# Power_PCB_final.net
KiCad netlist of a schematic drawn in EAGLE
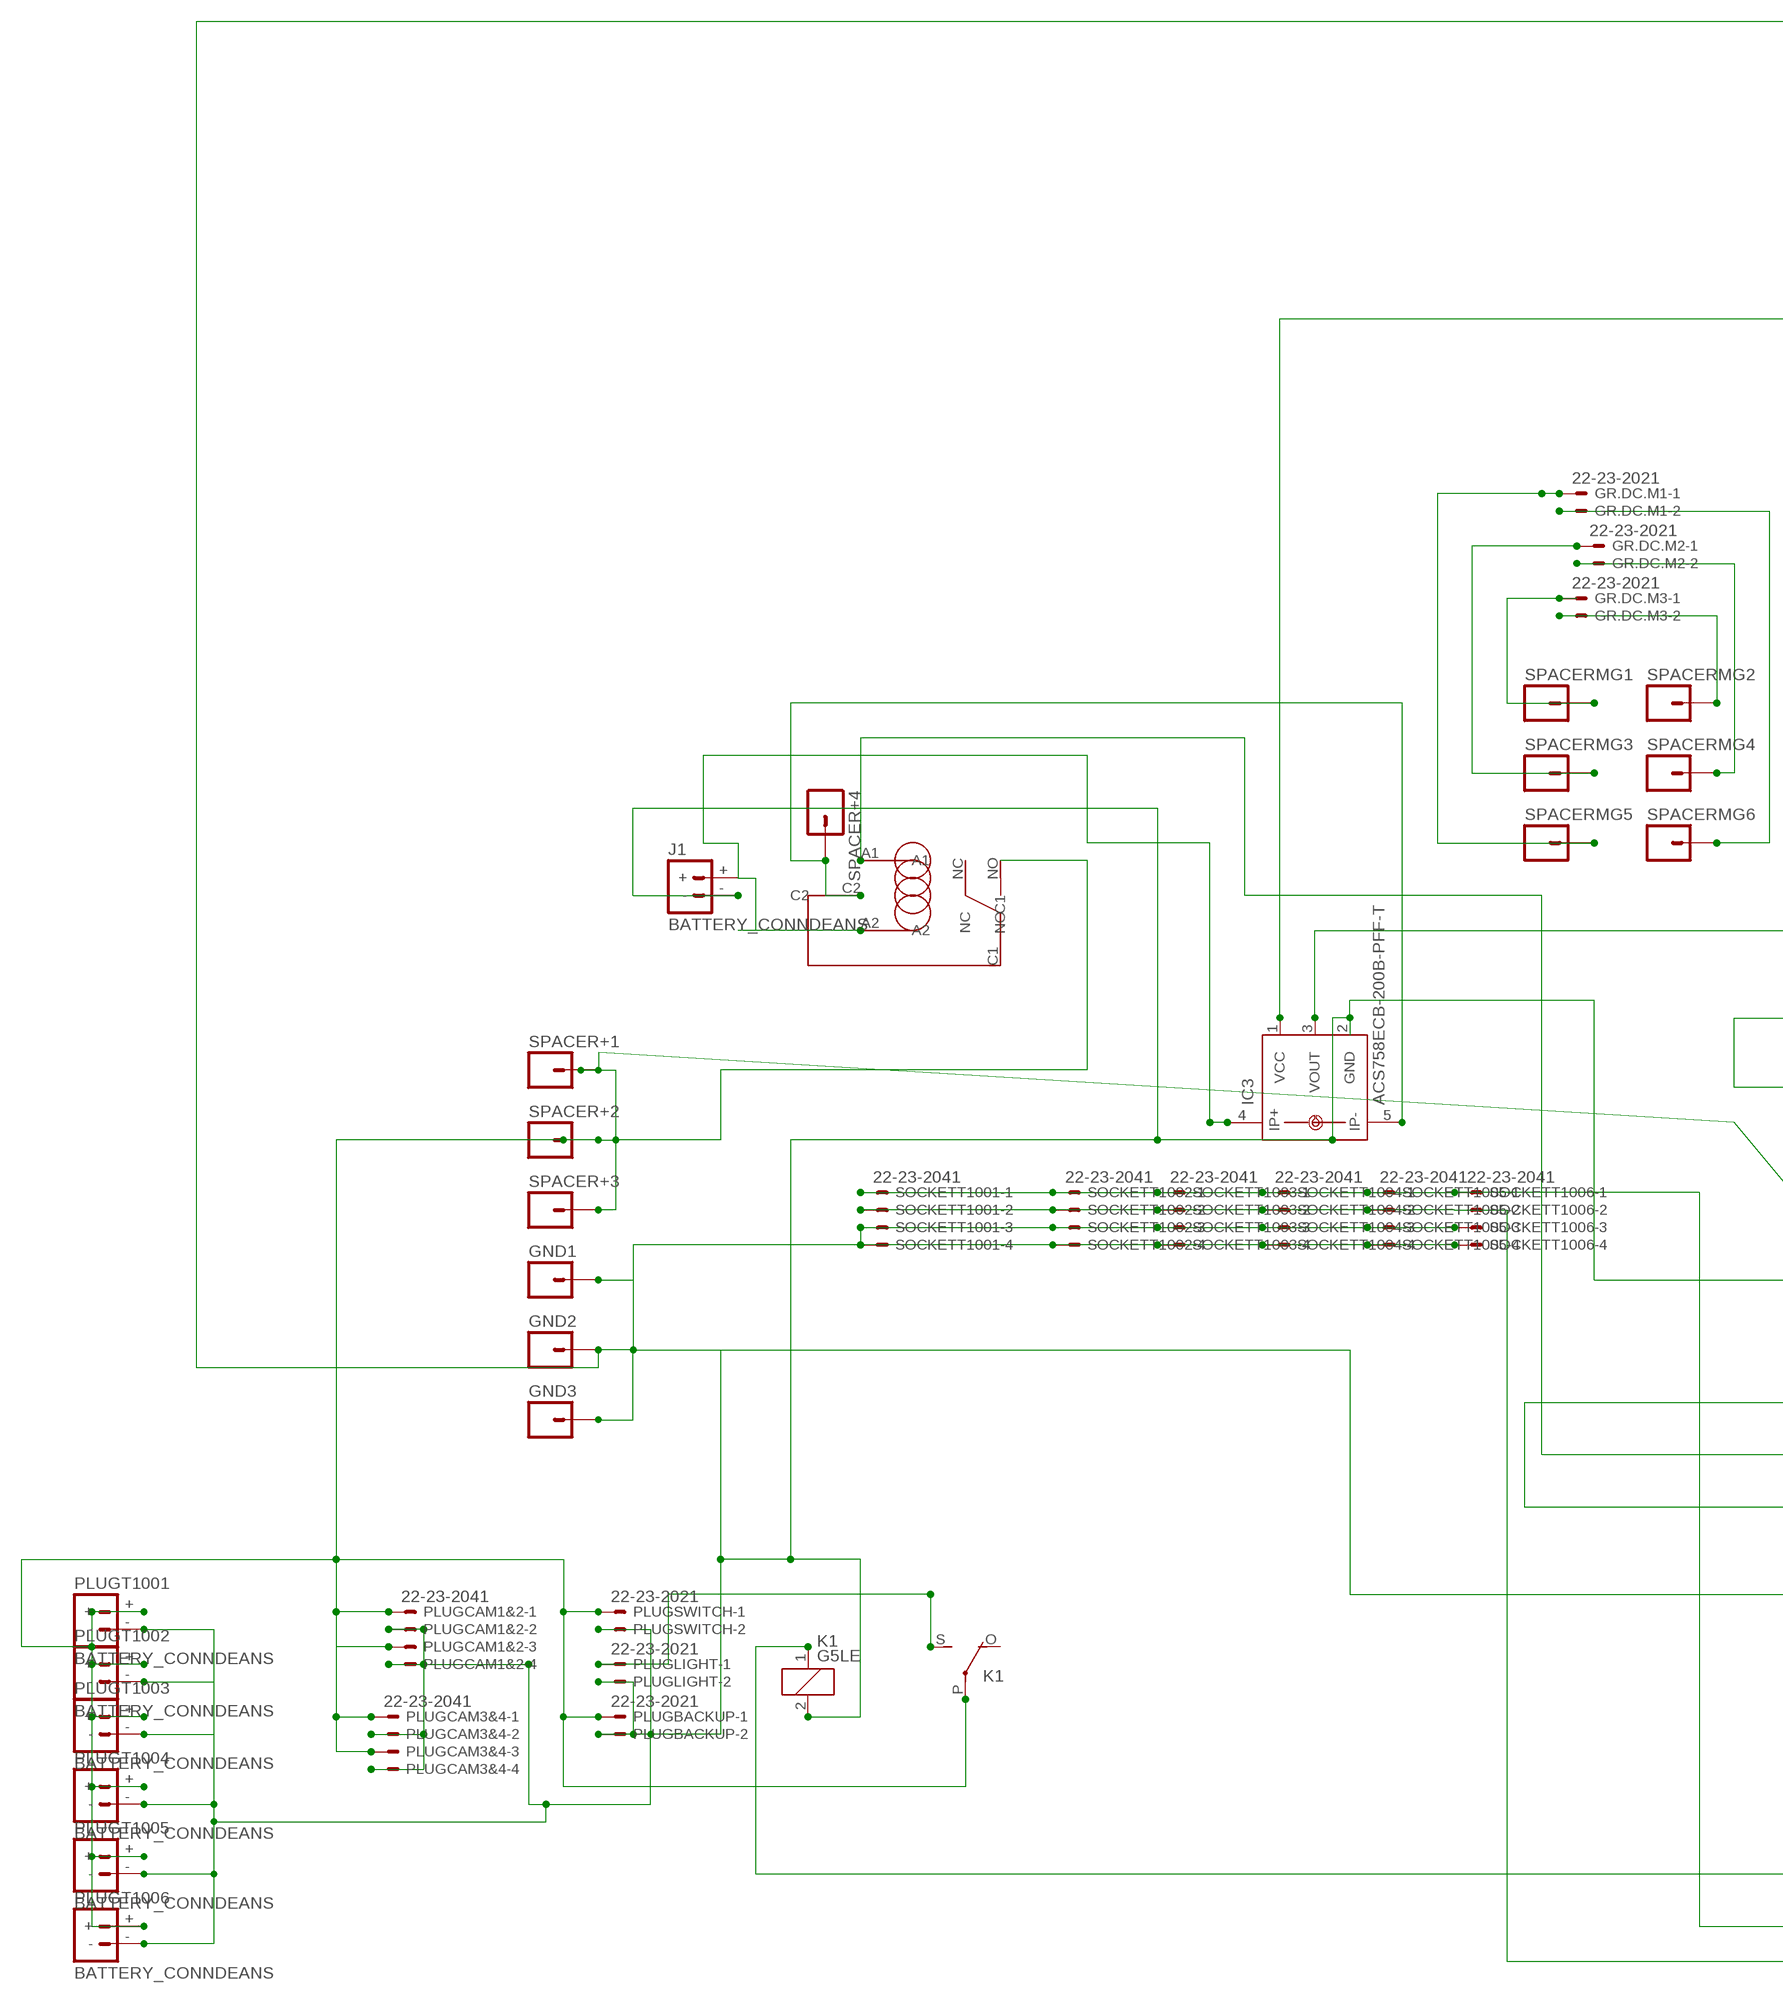
[diagram p0: schematic, sheet 1, part 1 of 2]
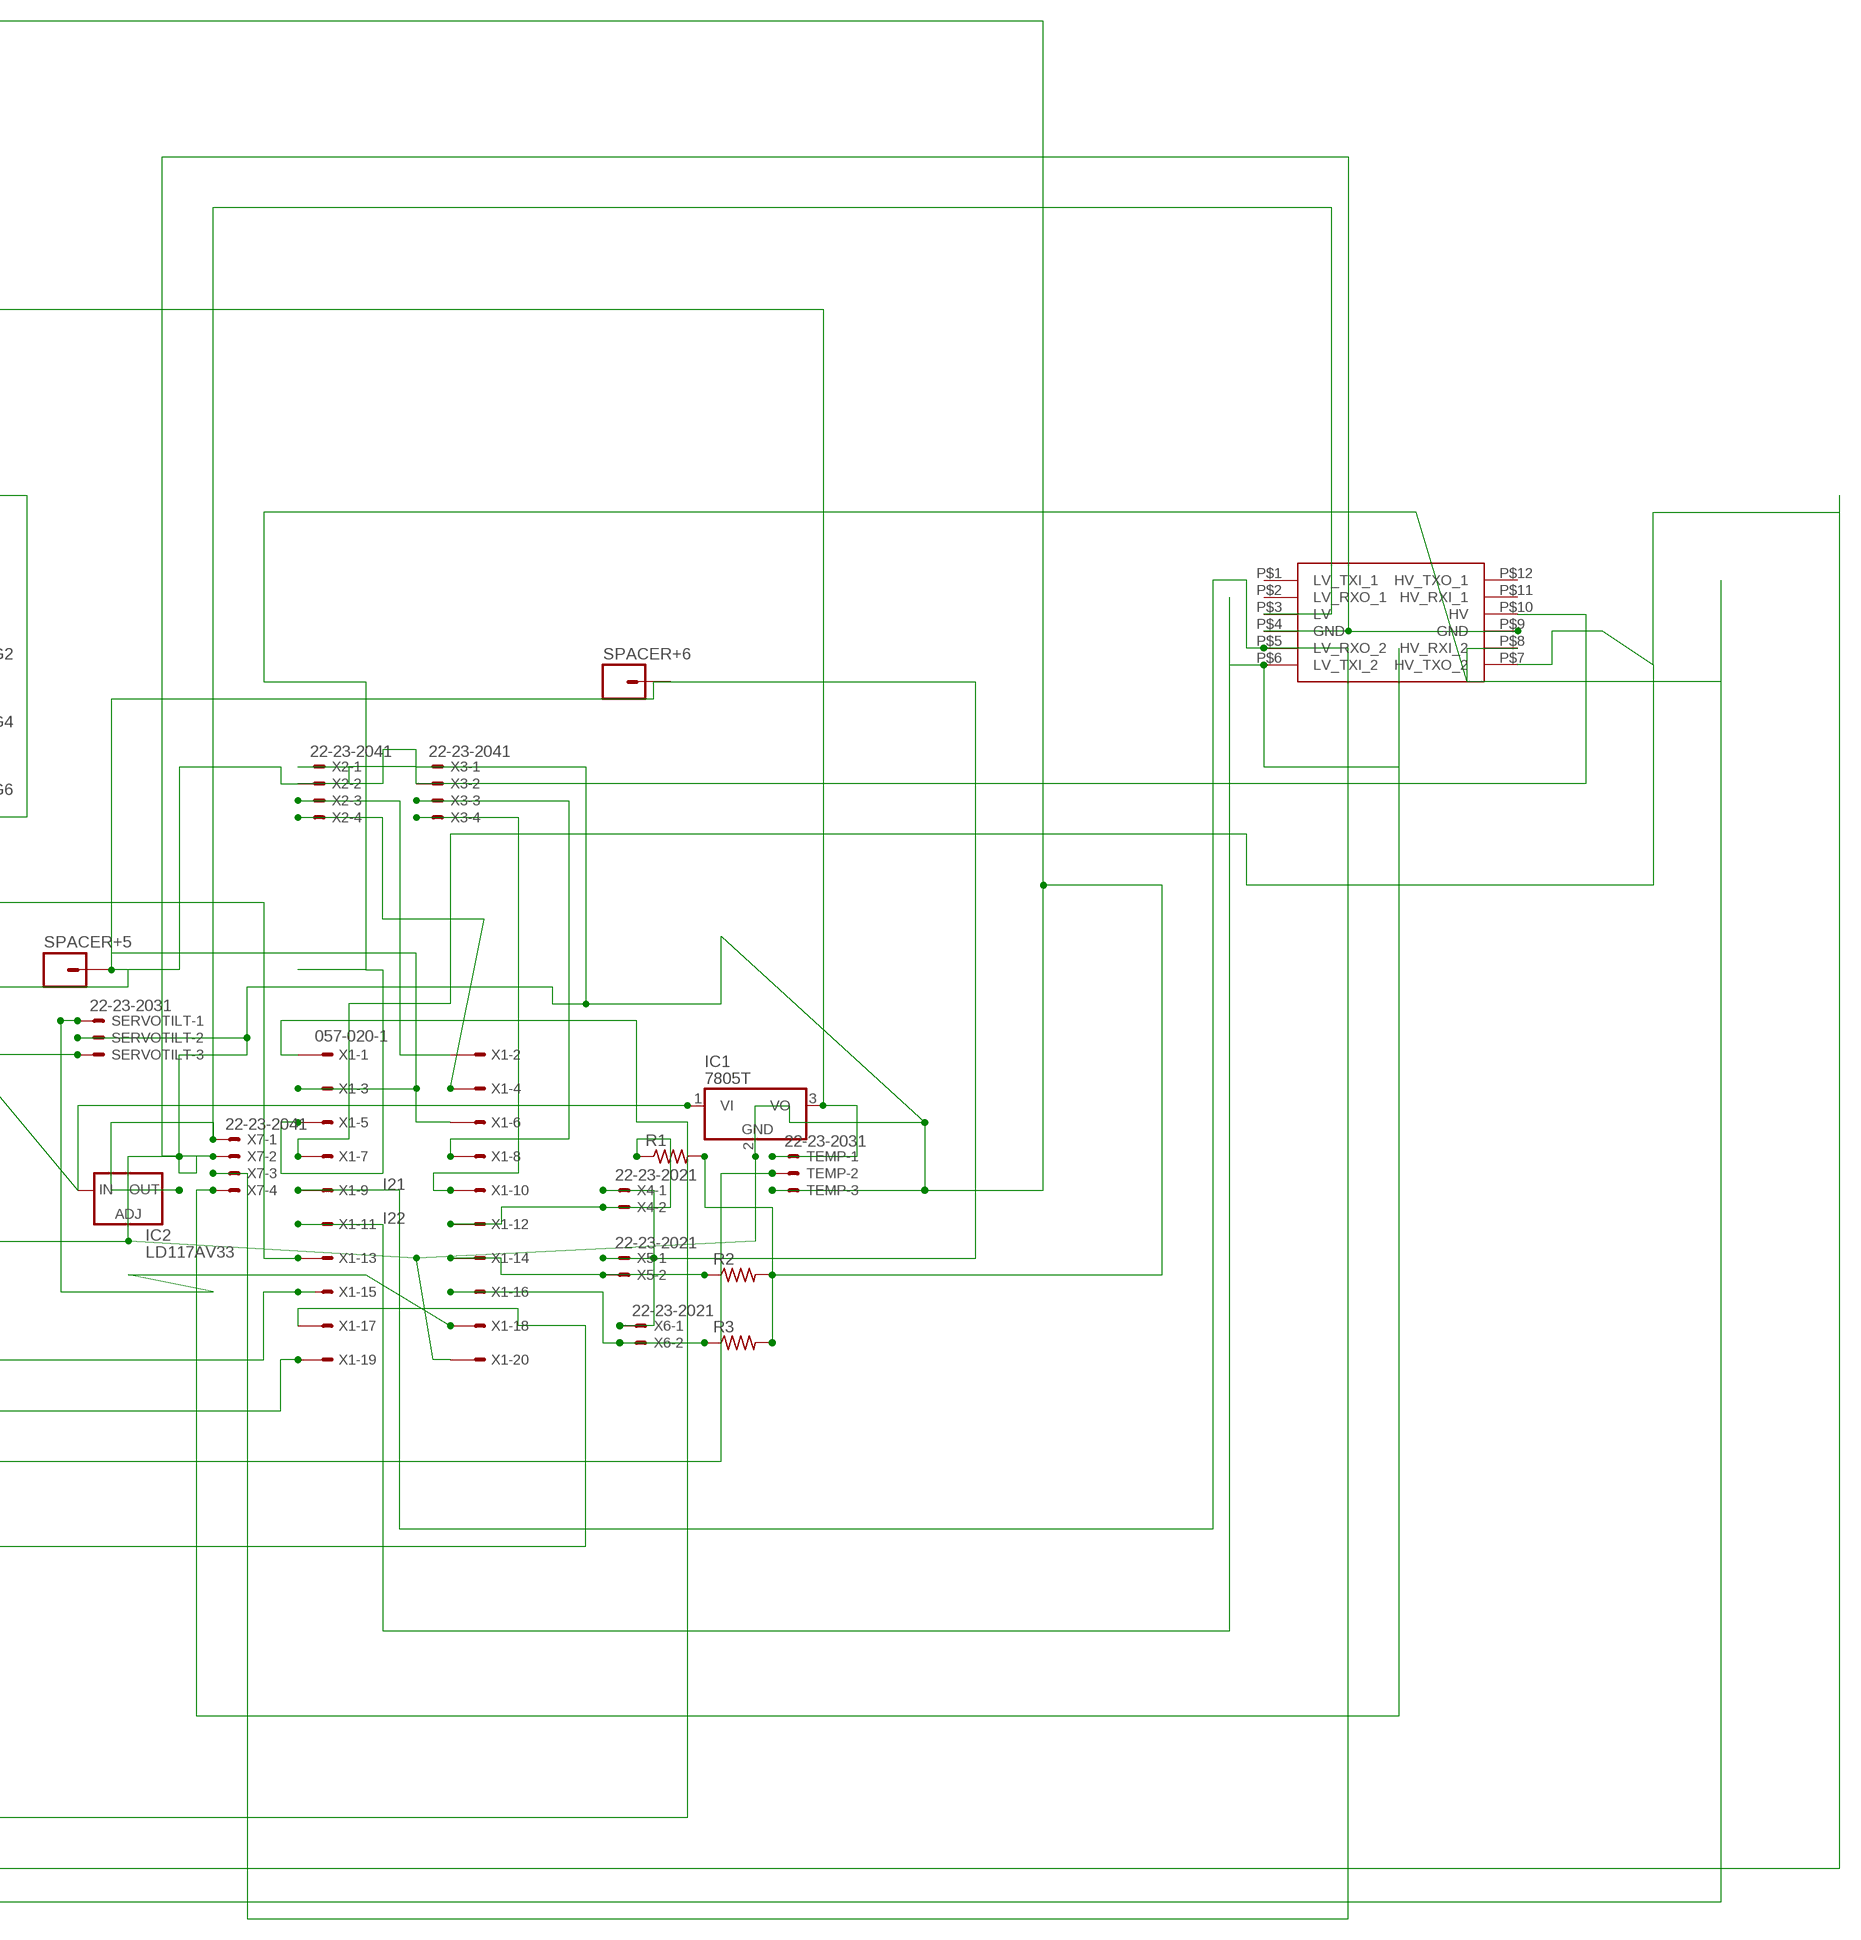
[diagram p1: schematic, sheet 1, part 2 of 2]

(export (version "E")
  (design (tool "Eeschema 10.0.6"))
  (components
    (comp (ref "GND1")
      (value "M01PTH_2MM")
      (footprint "eagle-import:1X01_2MM")
      (libsource (lib "eagle-import") (part "M01PTH_2MM"))
    )
    (comp (ref "GND2")
      (value "M01PTH_2MM")
      (footprint "eagle-import:1X01_2MM")
      (libsource (lib "eagle-import") (part "M01PTH_2MM"))
    )
    (comp (ref "GND3")
      (value "M01PTH_2MM")
      (footprint "eagle-import:1X01_2MM")
      (libsource (lib "eagle-import") (part "M01PTH_2MM"))
    )
    (comp (ref "GR.DC.M1")
      (value "22-23-2021")
      (footprint "eagle-import:22-23-2021")
      (fields (field (name "MF") "MOLEX"))
      (libsource (lib "eagle-import") (part "22-23-2021"))
    )
    (comp (ref "GR.DC.M2")
      (value "22-23-2021")
      (footprint "eagle-import:22-23-2021")
      (fields (field (name "MF") "MOLEX"))
      (libsource (lib "eagle-import") (part "22-23-2021"))
    )
    (comp (ref "GR.DC.M3")
      (value "22-23-2021")
      (footprint "eagle-import:22-23-2021")
      (fields (field (name "MF") "MOLEX"))
      (libsource (lib "eagle-import") (part "22-23-2021"))
    )
    (comp (ref "IC1")
      (value "7805T")
      (footprint "eagle-import:TO220H")
      (libsource (lib "eagle-import") (part "78T05"))
    )
    (comp (ref "IC2")
      (value "LD117AV33")
      (footprint "eagle-import:TO220L1")
      (libsource (lib "eagle-import") (part "LD117A?V33"))
    )
    (comp (ref "IC3")
      (value "ACS758ECB-200B-PFF-T")
      (footprint "eagle-import:CB-PFF")
      (libsource (lib "eagle-import") (part "ACS758ECB-200B-PFF-T"))
    )
    (comp (ref "J1")
      (value "BATTERY_CONNDEANS")
      (footprint "eagle-import:DEANS")
      (libsource (lib "eagle-import") (part "BATTERY_CONNDEANS"))
    )
    (comp (ref "K1")
      (value "G5LE")
      (footprint "eagle-import:G5LE")
      (libsource (lib "eagle-import") (part "G5LE"))
    )
    (comp (ref "PLUGBACKUP")
      (value "22-23-2021")
      (footprint "eagle-import:22-23-2021")
      (fields (field (name "MF") "MOLEX"))
      (libsource (lib "eagle-import") (part "22-23-2021"))
    )
    (comp (ref "PLUGCAM1&2")
      (value "22-23-2041")
      (footprint "eagle-import:22-23-2041")
      (fields (field (name "MF") "MOLEX"))
      (libsource (lib "eagle-import") (part "22-23-2041"))
    )
    (comp (ref "PLUGCAM3&4")
      (value "22-23-2041")
      (footprint "eagle-import:22-23-2041")
      (fields (field (name "MF") "MOLEX"))
      (libsource (lib "eagle-import") (part "22-23-2041"))
    )
    (comp (ref "PLUGLIGHT")
      (value "22-23-2021")
      (footprint "eagle-import:22-23-2021")
      (fields (field (name "MF") "MOLEX"))
      (libsource (lib "eagle-import") (part "22-23-2021"))
    )
    (comp (ref "PLUGSWITCH")
      (value "22-23-2021")
      (footprint "eagle-import:22-23-2021")
      (fields (field (name "MF") "MOLEX"))
      (libsource (lib "eagle-import") (part "22-23-2021"))
    )
    (comp (ref "PLUGT1001")
      (value "BATTERY_CONNDEANS")
      (footprint "eagle-import:DEANS")
      (libsource (lib "eagle-import") (part "BATTERY_CONNDEANS"))
    )
    (comp (ref "PLUGT1002")
      (value "BATTERY_CONNDEANS")
      (footprint "eagle-import:DEANS")
      (libsource (lib "eagle-import") (part "BATTERY_CONNDEANS"))
    )
    (comp (ref "PLUGT1003")
      (value "BATTERY_CONNDEANS")
      (footprint "eagle-import:DEANS")
      (libsource (lib "eagle-import") (part "BATTERY_CONNDEANS"))
    )
    (comp (ref "PLUGT1004")
      (value "BATTERY_CONNDEANS")
      (footprint "eagle-import:DEANS")
      (libsource (lib "eagle-import") (part "BATTERY_CONNDEANS"))
    )
    (comp (ref "PLUGT1005")
      (value "BATTERY_CONNDEANS")
      (footprint "eagle-import:DEANS")
      (libsource (lib "eagle-import") (part "BATTERY_CONNDEANS"))
    )
    (comp (ref "PLUGT1006")
      (value "BATTERY_CONNDEANS")
      (footprint "eagle-import:DEANS")
      (libsource (lib "eagle-import") (part "BATTERY_CONNDEANS"))
    )
    (comp (ref "R1")
      (value "R-US_0207/10")
      (footprint "eagle-import:0207_10")
      (libsource (lib "eagle-import") (part "R-US_0207/10"))
    )
    (comp (ref "R2")
      (value "R-US_0207/10")
      (footprint "eagle-import:0207_10")
      (libsource (lib "eagle-import") (part "R-US_0207/10"))
    )
    (comp (ref "R3")
      (value "R-US_0207/10")
      (footprint "eagle-import:0207_10")
      (libsource (lib "eagle-import") (part "R-US_0207/10"))
    )
    (comp (ref "SERVOTILT")
      (value "22-23-2031")
      (footprint "eagle-import:22-23-2031")
      (fields (field (name "MF") "MOLEX"))
      (libsource (lib "eagle-import") (part "22-23-2031"))
    )
    (comp (ref "SOCKETT1001")
      (value "22-23-2041")
      (footprint "eagle-import:22-23-2041")
      (fields (field (name "MF") "MOLEX"))
      (libsource (lib "eagle-import") (part "22-23-2041"))
    )
    (comp (ref "SOCKETT1002")
      (value "22-23-2041")
      (footprint "eagle-import:22-23-2041")
      (fields (field (name "MF") "MOLEX"))
      (libsource (lib "eagle-import") (part "22-23-2041"))
    )
    (comp (ref "SOCKETT1003")
      (value "22-23-2041")
      (footprint "eagle-import:22-23-2041")
      (fields (field (name "MF") "MOLEX"))
      (libsource (lib "eagle-import") (part "22-23-2041"))
    )
    (comp (ref "SOCKETT1004")
      (value "22-23-2041")
      (footprint "eagle-import:22-23-2041")
      (fields (field (name "MF") "MOLEX"))
      (libsource (lib "eagle-import") (part "22-23-2041"))
    )
    (comp (ref "SOCKETT1005")
      (value "22-23-2041")
      (footprint "eagle-import:22-23-2041")
      (fields (field (name "MF") "MOLEX"))
      (libsource (lib "eagle-import") (part "22-23-2041"))
    )
    (comp (ref "SOCKETT1006")
      (value "22-23-2041")
      (footprint "eagle-import:22-23-2041")
      (fields (field (name "MF") "MOLEX"))
      (libsource (lib "eagle-import") (part "22-23-2041"))
    )
    (comp (ref "SPACER+1")
      (value "M01PTH_2MM")
      (footprint "eagle-import:1X01_2MM")
      (libsource (lib "eagle-import") (part "M01PTH_2MM"))
    )
    (comp (ref "SPACER+2")
      (value "M01PTH_2MM")
      (footprint "eagle-import:1X01_2MM")
      (libsource (lib "eagle-import") (part "M01PTH_2MM"))
    )
    (comp (ref "SPACER+3")
      (value "M01PTH_2MM")
      (footprint "eagle-import:1X01_2MM")
      (libsource (lib "eagle-import") (part "M01PTH_2MM"))
    )
    (comp (ref "SPACER+4")
      (value "M01PTH_2MM")
      (footprint "eagle-import:1X01_2MM")
      (libsource (lib "eagle-import") (part "M01PTH_2MM"))
    )
    (comp (ref "SPACER+5")
      (value "M01PTH_2MM")
      (footprint "eagle-import:1X01_2MM")
      (libsource (lib "eagle-import") (part "M01PTH_2MM"))
    )
    (comp (ref "SPACER+6")
      (value "M01PTH_2MM")
      (footprint "eagle-import:1X01_2MM")
      (libsource (lib "eagle-import") (part "M01PTH_2MM"))
    )
    (comp (ref "SPACERMG1")
      (value "M01PTH_2MM")
      (footprint "eagle-import:1X01_2MM")
      (libsource (lib "eagle-import") (part "M01PTH_2MM"))
    )
    (comp (ref "SPACERMG2")
      (value "M01PTH_2MM")
      (footprint "eagle-import:1X01_2MM")
      (libsource (lib "eagle-import") (part "M01PTH_2MM"))
    )
    (comp (ref "SPACERMG3")
      (value "M01PTH_2MM")
      (footprint "eagle-import:1X01_2MM")
      (libsource (lib "eagle-import") (part "M01PTH_2MM"))
    )
    (comp (ref "SPACERMG4")
      (value "M01PTH_2MM")
      (footprint "eagle-import:1X01_2MM")
      (libsource (lib "eagle-import") (part "M01PTH_2MM"))
    )
    (comp (ref "SPACERMG5")
      (value "M01PTH_2MM")
      (footprint "eagle-import:1X01_2MM")
      (libsource (lib "eagle-import") (part "M01PTH_2MM"))
    )
    (comp (ref "SPACERMG6")
      (value "M01PTH_2MM")
      (footprint "eagle-import:1X01_2MM")
      (libsource (lib "eagle-import") (part "M01PTH_2MM"))
    )
    (comp (ref "TEMP")
      (value "22-23-2031")
      (footprint "eagle-import:22-23-2031")
      (fields (field (name "MF") "MOLEX"))
      (libsource (lib "eagle-import") (part "22-23-2031"))
    )
    (comp (ref "U$1")
      (value "30A_RELAY")
      (footprint "eagle-import:30A_RELAY")
      (libsource (lib "eagle-import") (part "30A_RELAY"))
    )
    (comp (ref "U$2")
      (value "LOGIC_LEVEL_CONVERTER")
      (footprint "eagle-import:LOGIC_LEVEL_CONVERTER")
      (libsource (lib "eagle-import") (part "LOGIC_LEVEL_CONVERTER"))
    )
    (comp (ref "X1")
      (value "057-020-1")
      (footprint "eagle-import:057-020-1")
      (libsource (lib "eagle-import") (part "057-020-1"))
    )
    (comp (ref "X2")
      (value "22-23-2041")
      (footprint "eagle-import:22-23-2041")
      (fields (field (name "MF") "MOLEX"))
      (libsource (lib "eagle-import") (part "22-23-2041"))
    )
    (comp (ref "X3")
      (value "22-23-2041")
      (footprint "eagle-import:22-23-2041")
      (fields (field (name "MF") "MOLEX"))
      (libsource (lib "eagle-import") (part "22-23-2041"))
    )
    (comp (ref "X4")
      (value "22-23-2021")
      (footprint "eagle-import:22-23-2021")
      (fields (field (name "MF") "MOLEX"))
      (libsource (lib "eagle-import") (part "22-23-2021"))
    )
    (comp (ref "X5")
      (value "22-23-2021")
      (footprint "eagle-import:22-23-2021")
      (fields (field (name "MF") "MOLEX"))
      (libsource (lib "eagle-import") (part "22-23-2021"))
    )
    (comp (ref "X6")
      (value "22-23-2021")
      (footprint "eagle-import:22-23-2021")
      (fields (field (name "MF") "MOLEX"))
      (libsource (lib "eagle-import") (part "22-23-2021"))
    )
    (comp (ref "X7")
      (value "22-23-2041")
      (footprint "eagle-import:22-23-2041")
      (fields (field (name "MF") "MOLEX"))
      (libsource (lib "eagle-import") (part "22-23-2041"))
    )
  )
  (nets
    (net (code "1") (name "/I21") (class "Default")
      (node (ref "U$2") (pin "P$5") (pinfunction "LV_RXO_2_P$5") (pintype "bidirectional"))
      (node (ref "X1") (pin "9") (pinfunction "S_9") (pintype "passive"))
      (node (ref "X7") (pin "3") (pinfunction "S_3") (pintype "passive"))
    )
    (net (code "2") (name "/I22") (class "Default")
      (node (ref "U$2") (pin "P$6") (pinfunction "LV_TXI_2_P$6") (pintype "bidirectional"))
      (node (ref "X1") (pin "11") (pinfunction "S_11") (pintype "passive"))
      (node (ref "X7") (pin "4") (pinfunction "S_4") (pintype "passive"))
    )
    (net (code "3") (name "Net-(GR.DC.M1A-S)") (class "Default")
      (node (ref "GR.DC.M1") (pin "1") (pinfunction "S_1") (pintype "passive"))
      (node (ref "SPACERMG5") (pin "1") (pinfunction "1_1") (pintype "passive"))
    )
    (net (code "4") (name "Net-(GR.DC.M1B-S)") (class "Default")
      (node (ref "GR.DC.M1") (pin "2") (pinfunction "S_2") (pintype "passive"))
      (node (ref "SPACERMG6") (pin "1") (pinfunction "1_1") (pintype "passive"))
    )
    (net (code "5") (name "Net-(GR.DC.M2A-S)") (class "Default")
      (node (ref "GR.DC.M2") (pin "1") (pinfunction "S_1") (pintype "passive"))
      (node (ref "SPACERMG3") (pin "1") (pinfunction "1_1") (pintype "passive"))
    )
    (net (code "6") (name "Net-(GR.DC.M2B-S)") (class "Default")
      (node (ref "GR.DC.M2") (pin "2") (pinfunction "S_2") (pintype "passive"))
      (node (ref "SPACERMG4") (pin "1") (pinfunction "1_1") (pintype "passive"))
    )
    (net (code "7") (name "Net-(GR.DC.M3A-S)") (class "Default")
      (node (ref "GR.DC.M3") (pin "1") (pinfunction "S_1") (pintype "passive"))
      (node (ref "SPACERMG1") (pin "1") (pinfunction "1_1") (pintype "passive"))
    )
    (net (code "8") (name "Net-(GR.DC.M3B-S)") (class "Default")
      (node (ref "GR.DC.M3") (pin "2") (pinfunction "S_2") (pintype "passive"))
      (node (ref "SPACERMG2") (pin "1") (pinfunction "1_1") (pintype "passive"))
    )
    (net (code "9") (name "Net-(IC1-GND)") (class "Default")
      (node (ref "GND1") (pin "1") (pinfunction "1_1") (pintype "passive"))
      (node (ref "GND2") (pin "1") (pinfunction "1_1") (pintype "passive"))
      (node (ref "GND3") (pin "1") (pinfunction "1_1") (pintype "passive"))
      (node (ref "IC1") (pin "2") (pinfunction "GND_2") (pintype "passive"))
      (node (ref "IC2") (pin "1") (pinfunction "ADJ_1") (pintype "input"))
      (node (ref "IC3") (pin "2") (pinfunction "GND_2") (pintype "power_in"))
      (node (ref "J1") (pin "-") (pinfunction "-_-") (pintype "passive"))
      (node (ref "K1") (pin "2") (pinfunction "2_2") (pintype "passive"))
      (node (ref "PLUGBACKUP") (pin "2") (pinfunction "S_2") (pintype "passive"))
      (node (ref "PLUGCAM1&2") (pin "2") (pinfunction "S_2") (pintype "passive"))
      (node (ref "PLUGCAM1&2") (pin "4") (pinfunction "S_4") (pintype "passive"))
      (node (ref "PLUGCAM3&4") (pin "2") (pinfunction "S_2") (pintype "passive"))
      (node (ref "PLUGCAM3&4") (pin "4") (pinfunction "S_4") (pintype "passive"))
      (node (ref "PLUGLIGHT") (pin "2") (pinfunction "S_2") (pintype "passive"))
      (node (ref "PLUGSWITCH") (pin "2") (pinfunction "S_2") (pintype "passive"))
      (node (ref "PLUGT1001") (pin "-") (pinfunction "-_-") (pintype "passive"))
      (node (ref "PLUGT1002") (pin "-") (pinfunction "-_-") (pintype "passive"))
      (node (ref "PLUGT1003") (pin "-") (pinfunction "-_-") (pintype "passive"))
      (node (ref "PLUGT1004") (pin "-") (pinfunction "-_-") (pintype "passive"))
      (node (ref "PLUGT1005") (pin "-") (pinfunction "-_-") (pintype "passive"))
      (node (ref "PLUGT1006") (pin "-") (pinfunction "-_-") (pintype "passive"))
      (node (ref "R1") (pin "2") (pinfunction "2_2") (pintype "passive"))
      (node (ref "R2") (pin "2") (pinfunction "2_2") (pintype "passive"))
      (node (ref "R3") (pin "2") (pinfunction "2_2") (pintype "passive"))
      (node (ref "SERVOTILT") (pin "2") (pinfunction "S_2") (pintype "passive"))
      (node (ref "SOCKETT1001") (pin "3") (pinfunction "S_3") (pintype "passive"))
      (node (ref "SOCKETT1001") (pin "4") (pinfunction "S_4") (pintype "passive"))
      (node (ref "SOCKETT1002") (pin "3") (pinfunction "S_3") (pintype "passive"))
      (node (ref "SOCKETT1002") (pin "4") (pinfunction "S_4") (pintype "passive"))
      (node (ref "SOCKETT1003") (pin "3") (pinfunction "S_3") (pintype "passive"))
      (node (ref "SOCKETT1003") (pin "4") (pinfunction "S_4") (pintype "passive"))
      (node (ref "SOCKETT1004") (pin "3") (pinfunction "S_3") (pintype "passive"))
      (node (ref "SOCKETT1004") (pin "4") (pinfunction "S_4") (pintype "passive"))
      (node (ref "SOCKETT1005") (pin "3") (pinfunction "S_3") (pintype "passive"))
      (node (ref "SOCKETT1005") (pin "4") (pinfunction "S_4") (pintype "passive"))
      (node (ref "SOCKETT1006") (pin "3") (pinfunction "S_3") (pintype "passive"))
      (node (ref "SOCKETT1006") (pin "4") (pinfunction "S_4") (pintype "passive"))
      (node (ref "TEMP") (pin "3") (pinfunction "S_3") (pintype "passive"))
      (node (ref "U$2") (pin "P$4") (pinfunction "GND_P$4") (pintype "bidirectional"))
      (node (ref "U$2") (pin "P$9") (pinfunction "GND_P$9") (pintype "bidirectional"))
      (node (ref "X1") (pin "17") (pinfunction "S_17") (pintype "passive"))
      (node (ref "X1") (pin "20") (pinfunction "S_20") (pintype "passive"))
      (node (ref "X2") (pin "1") (pinfunction "S_1") (pintype "passive"))
      (node (ref "X3") (pin "1") (pinfunction "S_1") (pintype "passive"))
      (node (ref "X7") (pin "2") (pinfunction "S_2") (pintype "passive"))
    )
    (net (code "10") (name "Net-(IC1-VI)") (class "Default")
      (node (ref "IC1") (pin "1") (pinfunction "VI_1") (pintype "input"))
      (node (ref "IC2") (pin "3") (pinfunction "IN_3") (pintype "input"))
      (node (ref "K1") (pin "P") (pinfunction "P_P") (pintype "passive"))
      (node (ref "PLUGBACKUP") (pin "1") (pinfunction "S_1") (pintype "passive"))
      (node (ref "PLUGCAM1&2") (pin "1") (pinfunction "S_1") (pintype "passive"))
      (node (ref "PLUGCAM1&2") (pin "3") (pinfunction "S_3") (pintype "passive"))
      (node (ref "PLUGCAM3&4") (pin "1") (pinfunction "S_1") (pintype "passive"))
      (node (ref "PLUGCAM3&4") (pin "3") (pinfunction "S_3") (pintype "passive"))
      (node (ref "PLUGSWITCH") (pin "1") (pinfunction "S_1") (pintype "passive"))
      (node (ref "PLUGT1001") (pin "+") (pinfunction "+_+") (pintype "passive"))
      (node (ref "PLUGT1002") (pin "+") (pinfunction "+_+") (pintype "passive"))
      (node (ref "PLUGT1003") (pin "+") (pinfunction "+_+") (pintype "passive"))
      (node (ref "PLUGT1004") (pin "+") (pinfunction "+_+") (pintype "passive"))
      (node (ref "PLUGT1005") (pin "+") (pinfunction "+_+") (pintype "passive"))
      (node (ref "PLUGT1006") (pin "+") (pinfunction "+_+") (pintype "passive"))
      (node (ref "SPACER+1") (pin "1") (pinfunction "1_1") (pintype "passive"))
      (node (ref "SPACER+2") (pin "1") (pinfunction "1_1") (pintype "passive"))
      (node (ref "SPACER+3") (pin "1") (pinfunction "1_1") (pintype "passive"))
      (node (ref "U$1") (pin "NO") (pinfunction "NO_NO") (pintype "bidirectional"))
    )
    (net (code "11") (name "Net-(IC1-VO)") (class "Default")
      (node (ref "IC1") (pin "3") (pinfunction "VO_3") (pintype "passive"))
      (node (ref "IC3") (pin "1") (pinfunction "VCC_1") (pintype "power_in"))
      (node (ref "TEMP") (pin "1") (pinfunction "S_1") (pintype "passive"))
    )
    (net (code "12") (name "Net-(IC2-OUT)") (class "Default")
      (node (ref "IC2") (pin "2") (pinfunction "OUT_2") (pintype "passive"))
      (node (ref "U$2") (pin "P$3") (pinfunction "LV_P$3") (pintype "bidirectional"))
      (node (ref "X7") (pin "1") (pinfunction "S_1") (pintype "passive"))
    )
    (net (code "13") (name "Net-(IC3-IP+)") (class "Default")
      (node (ref "IC3") (pin "4") (pinfunction "IP+_4") (pintype "passive"))
      (node (ref "J1") (pin "+") (pinfunction "+_+") (pintype "passive"))
      (node (ref "U$1") (pin "A2") (pinfunction "A2_A2") (pintype "bidirectional"))
    )
    (net (code "14") (name "Net-(IC3-IP-)") (class "Default")
      (node (ref "IC3") (pin "5") (pinfunction "IP-_5") (pintype "passive"))
      (node (ref "SPACER+4") (pin "1") (pinfunction "1_1") (pintype "passive"))
      (node (ref "U$1") (pin "C2") (pinfunction "C2_C2") (pintype "bidirectional"))
    )
    (net (code "15") (name "Net-(IC3-VOUT)") (class "Default")
      (node (ref "IC3") (pin "3") (pinfunction "VOUT_3") (pintype "output"))
      (node (ref "X1") (pin "13") (pinfunction "S_13") (pintype "passive"))
    )
    (net (code "16") (name "Net-(PLUGLIGHTA-S)") (class "Default")
      (node (ref "K1") (pin "S") (pinfunction "S_S") (pintype "passive"))
      (node (ref "PLUGLIGHT") (pin "1") (pinfunction "S_1") (pintype "passive"))
    )
    (net (code "17") (name "Net-(SERVOTILTA-S)") (class "Default")
      (node (ref "SERVOTILT") (pin "1") (pinfunction "S_1") (pintype "passive"))
      (node (ref "X1") (pin "18") (pinfunction "S_18") (pintype "passive"))
    )
    (net (code "18") (name "Net-(SERVOTILTC-S)") (class "Default")
      (node (ref "SERVOTILT") (pin "3") (pinfunction "S_3") (pintype "passive"))
      (node (ref "SPACER+5") (pin "1") (pinfunction "1_1") (pintype "passive"))
      (node (ref "SPACER+6") (pin "1") (pinfunction "1_1") (pintype "passive"))
      (node (ref "U$2") (pin "P$10") (pinfunction "HV_P$10") (pintype "bidirectional"))
      (node (ref "X1") (pin "3") (pinfunction "S_3") (pintype "passive"))
      (node (ref "X1") (pin "6") (pinfunction "S_6") (pintype "passive"))
      (node (ref "X2") (pin "2") (pinfunction "S_2") (pintype "passive"))
      (node (ref "X3") (pin "2") (pinfunction "S_2") (pintype "passive"))
      (node (ref "X4") (pin "1") (pinfunction "S_1") (pintype "passive"))
      (node (ref "X5") (pin "1") (pinfunction "S_1") (pintype "passive"))
      (node (ref "X6") (pin "1") (pinfunction "S_1") (pintype "passive"))
    )
    (net (code "19") (name "Net-(SOCKETT1001A-S)") (class "Default")
      (node (ref "SOCKETT1001") (pin "1") (pinfunction "S_1") (pintype "passive"))
      (node (ref "SOCKETT1002") (pin "1") (pinfunction "S_1") (pintype "passive"))
      (node (ref "SOCKETT1003") (pin "1") (pinfunction "S_1") (pintype "passive"))
      (node (ref "SOCKETT1004") (pin "1") (pinfunction "S_1") (pintype "passive"))
      (node (ref "SOCKETT1005") (pin "1") (pinfunction "S_1") (pintype "passive"))
      (node (ref "SOCKETT1006") (pin "1") (pinfunction "S_1") (pintype "passive"))
      (node (ref "U$2") (pin "P$7") (pinfunction "HV_TXO_2_P$7") (pintype "bidirectional"))
      (node (ref "X1") (pin "7") (pinfunction "S_7") (pintype "passive"))
    )
    (net (code "20") (name "Net-(SOCKETT1001B-S)") (class "Default")
      (node (ref "SOCKETT1001") (pin "2") (pinfunction "S_2") (pintype "passive"))
      (node (ref "SOCKETT1002") (pin "2") (pinfunction "S_2") (pintype "passive"))
      (node (ref "SOCKETT1003") (pin "2") (pinfunction "S_2") (pintype "passive"))
      (node (ref "SOCKETT1004") (pin "2") (pinfunction "S_2") (pintype "passive"))
      (node (ref "SOCKETT1005") (pin "2") (pinfunction "S_2") (pintype "passive"))
      (node (ref "SOCKETT1006") (pin "2") (pinfunction "S_2") (pintype "passive"))
      (node (ref "U$2") (pin "P$8") (pinfunction "HV_RXI_2_P$8") (pintype "bidirectional"))
      (node (ref "X1") (pin "5") (pinfunction "S_5") (pintype "passive"))
    )
    (net (code "21") (name "Net-(TEMPB-S)") (class "Default")
      (node (ref "TEMP") (pin "2") (pinfunction "S_2") (pintype "passive"))
      (node (ref "X1") (pin "15") (pinfunction "S_15") (pintype "passive"))
    )
    (net (code "22") (name "Net-(X1A-S)") (class "Default")
      (node (ref "K1") (pin "1") (pinfunction "1_1") (pintype "passive"))
      (node (ref "X1") (pin "1") (pinfunction "S_1") (pintype "passive"))
    )
    (net (code "23") (name "Net-(X1B-S)") (class "Default")
      (node (ref "X1") (pin "10") (pinfunction "S_10") (pintype "passive"))
      (node (ref "X3") (pin "4") (pinfunction "S_4") (pintype "passive"))
    )
    (net (code "24") (name "Net-(X1D-S)") (class "Default")
      (node (ref "R1") (pin "1") (pinfunction "1_1") (pintype "passive"))
      (node (ref "X1") (pin "12") (pinfunction "S_12") (pintype "passive"))
      (node (ref "X4") (pin "2") (pinfunction "S_2") (pintype "passive"))
    )
    (net (code "25") (name "Net-(X1F-S)") (class "Default")
      (node (ref "R2") (pin "1") (pinfunction "1_1") (pintype "passive"))
      (node (ref "X1") (pin "14") (pinfunction "S_14") (pintype "passive"))
      (node (ref "X5") (pin "2") (pinfunction "S_2") (pintype "passive"))
    )
    (net (code "26") (name "Net-(X1H-S)") (class "Default")
      (node (ref "R3") (pin "1") (pinfunction "1_1") (pintype "passive"))
      (node (ref "X1") (pin "16") (pinfunction "S_16") (pintype "passive"))
      (node (ref "X6") (pin "2") (pinfunction "S_2") (pintype "passive"))
    )
    (net (code "27") (name "Net-(X1K-S)") (class "Default")
      (node (ref "U$1") (pin "A1") (pinfunction "A1_A1") (pintype "bidirectional"))
      (node (ref "X1") (pin "19") (pinfunction "S_19") (pintype "passive"))
    )
    (net (code "28") (name "Net-(X1L-S)") (class "Default")
      (node (ref "X1") (pin "2") (pinfunction "S_2") (pintype "passive"))
      (node (ref "X2") (pin "3") (pinfunction "S_3") (pintype "passive"))
    )
    (net (code "29") (name "Net-(X1O-S)") (class "Default")
      (node (ref "X1") (pin "4") (pinfunction "S_4") (pintype "passive"))
      (node (ref "X2") (pin "4") (pinfunction "S_4") (pintype "passive"))
    )
    (net (code "30") (name "Net-(X1S-S)") (class "Default")
      (node (ref "X1") (pin "8") (pinfunction "S_8") (pintype "passive"))
      (node (ref "X3") (pin "3") (pinfunction "S_3") (pintype "passive"))
    )
    (net (code "31") (name "unconnected-(IC3-PadIP+1)") (class "Default")
      (node (ref "IC3") (pin "IP+1") (pinfunction "IP+1_IP+1") (pintype "input"))
    )
    (net (code "32") (name "unconnected-(IC3-PadIP-1)") (class "Default")
      (node (ref "IC3") (pin "IP-1") (pinfunction "IP-1_IP-1") (pintype "input"))
    )
    (net (code "33") (name "unconnected-(K1-PadO)") (class "Default")
      (node (ref "K1") (pin "O") (pinfunction "O_O") (pintype "passive"))
    )
    (net (code "34") (name "unconnected-(U$1-PadC1)") (class "Default")
      (node (ref "U$1") (pin "C1") (pinfunction "C1_C1") (pintype "bidirectional"))
    )
    (net (code "35") (name "unconnected-(U$1-PadNC)") (class "Default")
      (node (ref "U$1") (pin "NC") (pinfunction "NC_NC") (pintype "bidirectional"))
    )
    (net (code "36") (name "unconnected-(U$2-HV_RXI_1-PadP$11)") (class "Default")
      (node (ref "U$2") (pin "P$11") (pinfunction "HV_RXI_1_P$11") (pintype "bidirectional"))
    )
    (net (code "37") (name "unconnected-(U$2-HV_TXO_1-PadP$12)") (class "Default")
      (node (ref "U$2") (pin "P$12") (pinfunction "HV_TXO_1_P$12") (pintype "bidirectional"))
    )
    (net (code "38") (name "unconnected-(U$2-LV_RXO_1-PadP$2)") (class "Default")
      (node (ref "U$2") (pin "P$2") (pinfunction "LV_RXO_1_P$2") (pintype "bidirectional"))
    )
    (net (code "39") (name "unconnected-(U$2-LV_TXI_1-PadP$1)") (class "Default")
      (node (ref "U$2") (pin "P$1") (pinfunction "LV_TXI_1_P$1") (pintype "bidirectional"))
    )
  )
)
